# SUP_1V.net
KiCad netlist of a schematic drawn in Altium Designer
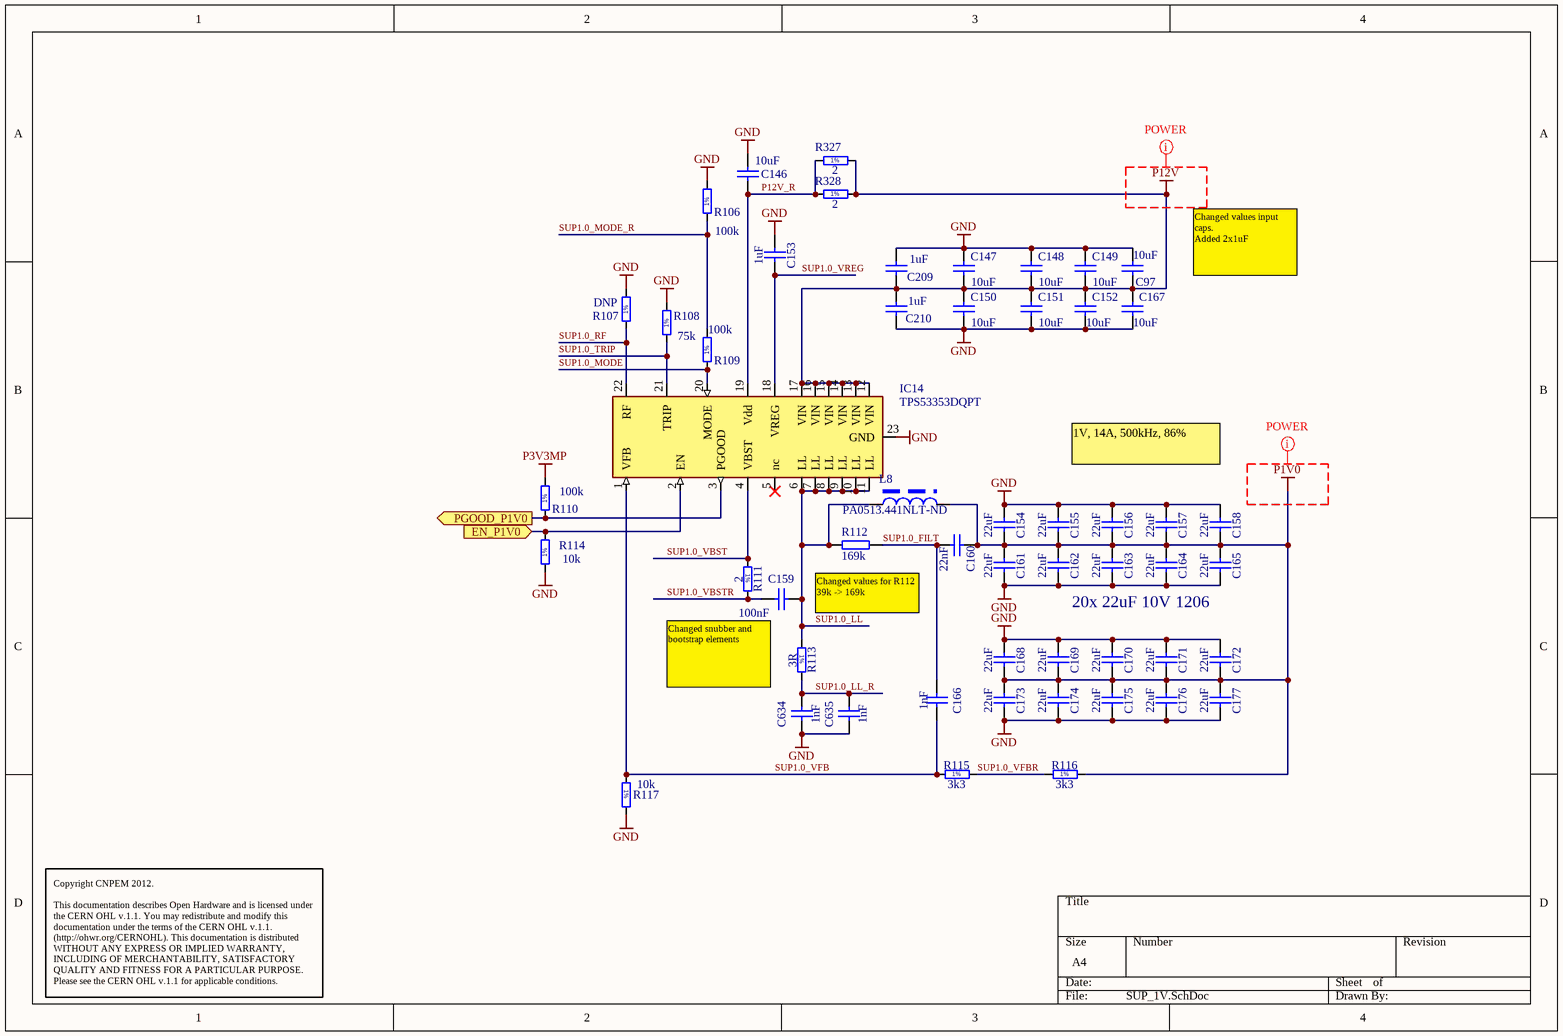
[diagram p0: SUP_1V.SchDoc]

(export (version "E")
  (design (tool "Eeschema 10.0.6"))
  (components
    (comp (ref "C97")
      (value "10uF")
      (footprint "CAPC2012X135N")
      (description "Non-polarised capacitor")
      (fields
        (field (name "PART NUMBER") "CC0805_10UF_16V_10%_X5R")
        (field (name "VOLTAGE") "16V")
        (field (name "AUTHOR") "CERN DEM JLC")
      )
      (libsource (lib "Capacitors") (part "Capacitor - non polarized"))
    )
    (comp (ref "C146")
      (value "10uF")
      (footprint "CAPC2012X135N")
      (description "Non-polarised capacitor")
      (fields
        (field (name "PART NUMBER") "CC0805_10UF_16V_10%_X5R")
        (field (name "VOLTAGE") "16V")
        (field (name "AUTHOR") "CERN DEM JLC")
      )
      (libsource (lib "Capacitors") (part "Capacitor - non polarized"))
    )
    (comp (ref "C147")
      (value "10uF")
      (footprint "CAPC2012X135N")
      (description "Non-polarised capacitor")
      (fields
        (field (name "PART NUMBER") "CC0805_10UF_16V_10%_X5R")
        (field (name "VOLTAGE") "16V")
        (field (name "AUTHOR") "CERN DEM JLC")
      )
      (libsource (lib "Capacitors") (part "Capacitor - non polarized"))
    )
    (comp (ref "C148")
      (value "10uF")
      (footprint "CAPC2012X135N")
      (description "Non-polarised capacitor")
      (fields
        (field (name "PART NUMBER") "CC0805_10UF_16V_10%_X5R")
        (field (name "VOLTAGE") "16V")
        (field (name "AUTHOR") "CERN DEM JLC")
      )
      (libsource (lib "Capacitors") (part "Capacitor - non polarized"))
    )
    (comp (ref "C149")
      (value "10uF")
      (footprint "CAPC2012X135N")
      (description "Non-polarised capacitor")
      (fields
        (field (name "PART NUMBER") "CC0805_10UF_16V_10%_X5R")
        (field (name "VOLTAGE") "16V")
        (field (name "AUTHOR") "CERN DEM JLC")
      )
      (libsource (lib "Capacitors") (part "Capacitor - non polarized"))
    )
    (comp (ref "C150")
      (value "10uF")
      (footprint "CAPC2012X135N")
      (description "Non-polarised capacitor")
      (fields
        (field (name "PART NUMBER") "CC0805_10UF_16V_10%_X5R")
        (field (name "VOLTAGE") "16V")
        (field (name "AUTHOR") "CERN DEM JLC")
      )
      (libsource (lib "Capacitors") (part "Capacitor - non polarized"))
    )
    (comp (ref "C151")
      (value "10uF")
      (footprint "CAPC2012X135N")
      (description "Non-polarised capacitor")
      (fields
        (field (name "PART NUMBER") "CC0805_10UF_16V_10%_X5R")
        (field (name "VOLTAGE") "16V")
        (field (name "AUTHOR") "CERN DEM JLC")
      )
      (libsource (lib "Capacitors") (part "Capacitor - non polarized"))
    )
    (comp (ref "C152")
      (value "10uF")
      (footprint "CAPC2012X135N")
      (description "Non-polarised capacitor")
      (fields
        (field (name "PART NUMBER") "CC0805_10UF_16V_10%_X5R")
        (field (name "VOLTAGE") "16V")
        (field (name "AUTHOR") "CERN DEM JLC")
      )
      (libsource (lib "Capacitors") (part "Capacitor - non polarized"))
    )
    (comp (ref "C153")
      (value "1uF")
      (footprint "CAPC1608X87N")
      (description "Non-polarised capacitor")
      (fields
        (field (name "PART NUMBER") "CC0603_1UF_16V_10%_X7R")
        (field (name "VOLTAGE") "16V")
        (field (name "AUTHOR") "CERN DEM JLC")
      )
      (libsource (lib "Capacitors") (part "Capacitor - non polarized"))
    )
    (comp (ref "C154")
      (value "22uF")
      (footprint "CAPC3216X180N")
      (description "Non-polarised capacitor")
      (fields
        (field (name "PART NUMBER") "CC1206_22UF_10V_10%_X7R")
        (field (name "VOLTAGE") "10V")
        (field (name "AUTHOR") "CERN DEM JLC")
      )
      (libsource (lib "Capacitors") (part "Capacitor - non polarized"))
    )
    (comp (ref "C155")
      (value "22uF")
      (footprint "CAPC3216X180N")
      (description "Non-polarised capacitor")
      (fields
        (field (name "PART NUMBER") "CC1206_22UF_10V_10%_X7R")
        (field (name "VOLTAGE") "10V")
        (field (name "AUTHOR") "CERN DEM JLC")
      )
      (libsource (lib "Capacitors") (part "Capacitor - non polarized"))
    )
    (comp (ref "C156")
      (value "22uF")
      (footprint "CAPC3216X180N")
      (description "Non-polarised capacitor")
      (fields
        (field (name "PART NUMBER") "CC1206_22UF_10V_10%_X7R")
        (field (name "VOLTAGE") "10V")
        (field (name "AUTHOR") "CERN DEM JLC")
      )
      (libsource (lib "Capacitors") (part "Capacitor - non polarized"))
    )
    (comp (ref "C157")
      (value "22uF")
      (footprint "CAPC3216X180N")
      (description "Non-polarised capacitor")
      (fields
        (field (name "PART NUMBER") "CC1206_22UF_10V_10%_X7R")
        (field (name "VOLTAGE") "10V")
        (field (name "AUTHOR") "CERN DEM JLC")
      )
      (libsource (lib "Capacitors") (part "Capacitor - non polarized"))
    )
    (comp (ref "C158")
      (value "22uF")
      (footprint "CAPC3216X180N")
      (description "Non-polarised capacitor")
      (fields
        (field (name "PART NUMBER") "CC1206_22UF_10V_10%_X7R")
        (field (name "VOLTAGE") "10V")
        (field (name "AUTHOR") "CERN DEM JLC")
      )
      (libsource (lib "Capacitors") (part "Capacitor - non polarized"))
    )
    (comp (ref "C159")
      (value "100nF")
      (footprint "CAPC1005X55N")
      (description "Non-polarised capacitor")
      (fields
        (field (name "PART NUMBER") "CC0402_100NF_16V_10%_X7R")
        (field (name "VOLTAGE") "16V")
        (field (name "AUTHOR") "CERN DEM JLC")
      )
      (libsource (lib "Capacitors") (part "Capacitor - non polarized"))
    )
    (comp (ref "C160")
      (value "22nF")
      (footprint "CAPC1608X87N")
      (description "Non-polarised capacitor")
      (fields
        (field (name "PART NUMBER") "CC0603_22NF_50V_10%_X7R")
        (field (name "VOLTAGE") "50V")
        (field (name "AUTHOR") "CERN DEM JLC")
      )
      (libsource (lib "Capacitors") (part "Capacitor - non polarized"))
    )
    (comp (ref "C161")
      (value "22uF")
      (footprint "CAPC3216X180N")
      (description "Non-polarised capacitor")
      (fields
        (field (name "PART NUMBER") "CC1206_22UF_10V_10%_X7R")
        (field (name "VOLTAGE") "10V")
        (field (name "AUTHOR") "CERN DEM JLC")
      )
      (libsource (lib "Capacitors") (part "Capacitor - non polarized"))
    )
    (comp (ref "C162")
      (value "22uF")
      (footprint "CAPC3216X180N")
      (description "Non-polarised capacitor")
      (fields
        (field (name "PART NUMBER") "CC1206_22UF_10V_10%_X7R")
        (field (name "VOLTAGE") "10V")
        (field (name "AUTHOR") "CERN DEM JLC")
      )
      (libsource (lib "Capacitors") (part "Capacitor - non polarized"))
    )
    (comp (ref "C163")
      (value "22uF")
      (footprint "CAPC3216X180N")
      (description "Non-polarised capacitor")
      (fields
        (field (name "PART NUMBER") "CC1206_22UF_10V_10%_X7R")
        (field (name "VOLTAGE") "10V")
        (field (name "AUTHOR") "CERN DEM JLC")
      )
      (libsource (lib "Capacitors") (part "Capacitor - non polarized"))
    )
    (comp (ref "C164")
      (value "22uF")
      (footprint "CAPC3216X180N")
      (description "Non-polarised capacitor")
      (fields
        (field (name "PART NUMBER") "CC1206_22UF_10V_10%_X7R")
        (field (name "VOLTAGE") "10V")
        (field (name "AUTHOR") "CERN DEM JLC")
      )
      (libsource (lib "Capacitors") (part "Capacitor - non polarized"))
    )
    (comp (ref "C165")
      (value "22uF")
      (footprint "CAPC3216X180N")
      (description "Non-polarised capacitor")
      (fields
        (field (name "PART NUMBER") "CC1206_22UF_10V_10%_X7R")
        (field (name "VOLTAGE") "10V")
        (field (name "AUTHOR") "CERN DEM JLC")
      )
      (libsource (lib "Capacitors") (part "Capacitor - non polarized"))
    )
    (comp (ref "C166")
      (value "1nF")
      (footprint "CAPC1005X55N")
      (description "Non-polarised capacitor")
      (fields
        (field (name "PART NUMBER") "CC0402_1NF_50V_10%_X7R")
        (field (name "VOLTAGE") "50V")
        (field (name "AUTHOR") "CERN DEM JLC")
      )
      (libsource (lib "Capacitors") (part "Capacitor - non polarized"))
    )
    (comp (ref "C167")
      (value "10uF")
      (footprint "CAPC2012X135N")
      (description "Non-polarised capacitor")
      (fields
        (field (name "PART NUMBER") "CC0805_10UF_16V_10%_X5R")
        (field (name "VOLTAGE") "16V")
        (field (name "AUTHOR") "CERN DEM JLC")
      )
      (libsource (lib "Capacitors") (part "Capacitor - non polarized"))
    )
    (comp (ref "C168")
      (value "22uF")
      (footprint "CAPC3216X180N")
      (description "Non-polarised capacitor")
      (fields
        (field (name "PART NUMBER") "CC1206_22UF_10V_10%_X7R")
        (field (name "VOLTAGE") "10V")
        (field (name "AUTHOR") "CERN DEM JLC")
      )
      (libsource (lib "Capacitors") (part "Capacitor - non polarized"))
    )
    (comp (ref "C169")
      (value "22uF")
      (footprint "CAPC3216X180N")
      (description "Non-polarised capacitor")
      (fields
        (field (name "PART NUMBER") "CC1206_22UF_10V_10%_X7R")
        (field (name "VOLTAGE") "10V")
        (field (name "AUTHOR") "CERN DEM JLC")
      )
      (libsource (lib "Capacitors") (part "Capacitor - non polarized"))
    )
    (comp (ref "C170")
      (value "22uF")
      (footprint "CAPC3216X180N")
      (description "Non-polarised capacitor")
      (fields
        (field (name "PART NUMBER") "CC1206_22UF_10V_10%_X7R")
        (field (name "VOLTAGE") "10V")
        (field (name "AUTHOR") "CERN DEM JLC")
      )
      (libsource (lib "Capacitors") (part "Capacitor - non polarized"))
    )
    (comp (ref "C171")
      (value "22uF")
      (footprint "CAPC3216X180N")
      (description "Non-polarised capacitor")
      (fields
        (field (name "PART NUMBER") "CC1206_22UF_10V_10%_X7R")
        (field (name "VOLTAGE") "10V")
        (field (name "AUTHOR") "CERN DEM JLC")
      )
      (libsource (lib "Capacitors") (part "Capacitor - non polarized"))
    )
    (comp (ref "C172")
      (value "22uF")
      (footprint "CAPC3216X180N")
      (description "Non-polarised capacitor")
      (fields
        (field (name "PART NUMBER") "CC1206_22UF_10V_10%_X7R")
        (field (name "VOLTAGE") "10V")
        (field (name "AUTHOR") "CERN DEM JLC")
      )
      (libsource (lib "Capacitors") (part "Capacitor - non polarized"))
    )
    (comp (ref "C173")
      (value "22uF")
      (footprint "CAPC3216X180N")
      (description "Non-polarised capacitor")
      (fields
        (field (name "PART NUMBER") "CC1206_22UF_10V_10%_X7R")
        (field (name "VOLTAGE") "10V")
        (field (name "AUTHOR") "CERN DEM JLC")
      )
      (libsource (lib "Capacitors") (part "Capacitor - non polarized"))
    )
    (comp (ref "C174")
      (value "22uF")
      (footprint "CAPC3216X180N")
      (description "Non-polarised capacitor")
      (fields
        (field (name "PART NUMBER") "CC1206_22UF_10V_10%_X7R")
        (field (name "VOLTAGE") "10V")
        (field (name "AUTHOR") "CERN DEM JLC")
      )
      (libsource (lib "Capacitors") (part "Capacitor - non polarized"))
    )
    (comp (ref "C175")
      (value "22uF")
      (footprint "CAPC3216X180N")
      (description "Non-polarised capacitor")
      (fields
        (field (name "PART NUMBER") "CC1206_22UF_10V_10%_X7R")
        (field (name "VOLTAGE") "10V")
        (field (name "AUTHOR") "CERN DEM JLC")
      )
      (libsource (lib "Capacitors") (part "Capacitor - non polarized"))
    )
    (comp (ref "C176")
      (value "22uF")
      (footprint "CAPC3216X180N")
      (description "Non-polarised capacitor")
      (fields
        (field (name "PART NUMBER") "CC1206_22UF_10V_10%_X7R")
        (field (name "VOLTAGE") "10V")
        (field (name "AUTHOR") "CERN DEM JLC")
      )
      (libsource (lib "Capacitors") (part "Capacitor - non polarized"))
    )
    (comp (ref "C177")
      (value "22uF")
      (footprint "CAPC3216X180N")
      (description "Non-polarised capacitor")
      (fields
        (field (name "PART NUMBER") "CC1206_22UF_10V_10%_X7R")
        (field (name "VOLTAGE") "10V")
        (field (name "AUTHOR") "CERN DEM JLC")
      )
      (libsource (lib "Capacitors") (part "Capacitor - non polarized"))
    )
    (comp (ref "C209")
      (value "1uF")
      (footprint "CAPC1608X87N")
      (description "Non-polarised capacitor")
      (fields
        (field (name "PART NUMBER") "CC0603_1UF_16V_10%_X7R")
        (field (name "VOLTAGE") "16V")
        (field (name "AUTHOR") "CERN DEM JLC")
      )
      (libsource (lib "Capacitors") (part "Capacitor - non polarized"))
    )
    (comp (ref "C210")
      (value "1uF")
      (footprint "CAPC1608X87N")
      (description "Non-polarised capacitor")
      (fields
        (field (name "PART NUMBER") "CC0603_1UF_16V_10%_X7R")
        (field (name "VOLTAGE") "16V")
        (field (name "AUTHOR") "CERN DEM JLC")
      )
      (libsource (lib "Capacitors") (part "Capacitor - non polarized"))
    )
    (comp (ref "C634")
      (value "1nF")
      (footprint "CAPC1005X55N")
      (description "Non-polarised capacitor")
      (fields
        (field (name "PART NUMBER") "CC0402_1NF_50V_10%_X7R")
        (field (name "VOLTAGE") "50V")
        (field (name "AUTHOR") "CERN DEM JLC")
      )
      (libsource (lib "Capacitors") (part "Capacitor - non polarized"))
    )
    (comp (ref "C635")
      (value "1nF")
      (footprint "CAPC1005X55N")
      (description "Non-polarised capacitor")
      (fields
        (field (name "PART NUMBER") "CC0402_1NF_50V_10%_X7R")
        (field (name "VOLTAGE") "50V")
        (field (name "AUTHOR") "CERN DEM JLC")
      )
      (libsource (lib "Capacitors") (part "Capacitor - non polarized"))
    )
    (comp (ref "IC14")
      (value "TPS53353DQPT")
      (footprint "LCCS50P600X500X150-22N")
      (description "High-Efficiency 20-A Synchronous Buck Converter with Eco-mode™")
      (libsource (lib "LIBRARY_SCH") (part "PM_TPS53353"))
    )
    (comp (ref "L8")
      (value "PA0513.441NLT-ND")
      (footprint "IND_PA0513")
      (description "440nH, 30A, 0.32mOhm")
      (libsource (lib "LIBRARY_SCH") (part "L_POWER_PA1513_440nH"))
    )
    (comp (ref "R106")
      (value "100k")
      (footprint "RESC1005X40N")
      (description "Resistor - 1%")
      (fields
        (field (name "PART NUMBER") "R0402_100K_1%_0.0625W_100PPM")
        (field (name "POWER") "0.0625W")
        (field (name "AUTHOR") "CERN DEM JLC")
      )
      (libsource (lib "Resistors") (part "Resistor - 1%"))
    )
    (comp (ref "R107")
      (value "DNP")
      (footprint "RESC1608X55N")
      (description "Resistor - 1%")
      (fields
        (field (name "PART NUMBER") "R0603_75K_1%_0.1W_100PPM")
        (field (name "POWER") "0.1W")
        (field (name "AUTHOR") "CERN DEM JLC")
      )
      (libsource (lib "Resistors") (part "Resistor - 1%"))
    )
    (comp (ref "R108")
      (value "75k")
      (footprint "RESC1608X55N")
      (description "Resistor - 1%")
      (fields
        (field (name "PART NUMBER") "R0603_75K_1%_0.1W_100PPM")
        (field (name "POWER") "0.1W")
        (field (name "AUTHOR") "CERN DEM JLC")
      )
      (libsource (lib "Resistors") (part "Resistor - 1%"))
    )
    (comp (ref "R109")
      (value "100k")
      (footprint "RESC1005X40N")
      (description "Resistor - 1%")
      (fields
        (field (name "PART NUMBER") "R0402_100K_1%_0.0625W_100PPM")
        (field (name "POWER") "0.0625W")
        (field (name "AUTHOR") "CERN DEM JLC")
      )
      (libsource (lib "Resistors") (part "Resistor - 1%"))
    )
    (comp (ref "R110")
      (value "100k")
      (footprint "RESC1005X40N")
      (description "Resistor - 1%")
      (fields
        (field (name "PART NUMBER") "R0402_100K_1%_0.0625W_100PPM")
        (field (name "POWER") "0.0625W")
        (field (name "AUTHOR") "CERN DEM JLC")
      )
      (libsource (lib "Resistors") (part "Resistor - 1%"))
    )
    (comp (ref "R111")
      (value "2")
      (footprint "RESC1608X55N")
      (description "Resistor - 1%")
      (fields
        (field (name "PART NUMBER") "R0603_2R_1%_0.1W_200PPM")
        (field (name "POWER") "0.1W")
        (field (name "AUTHOR") "CERN DEM JLC")
      )
      (libsource (lib "Resistors") (part "Resistor - 1%"))
    )
    (comp (ref "R112")
      (value "169k")
      (footprint "0603R")
      (description "SMD Resistor")
      (libsource (lib "LIBRARY_SCH") (part "RES_0603"))
    )
    (comp (ref "R113")
      (value "3R")
      (footprint "RESC3216X65N")
      (description "Resistor - 1%")
      (fields
        (field (name "PART NUMBER") "R1206_3R_1%_0.25W_200PPM")
        (field (name "POWER") "0.25W")
        (field (name "AUTHOR") "CERN DEM JLC")
      )
      (libsource (lib "Resistors") (part "Resistor - 1%"))
    )
    (comp (ref "R114")
      (value "10k")
      (footprint "RESC1005X40N")
      (description "Resistor - 1%")
      (fields
        (field (name "PART NUMBER") "R0402_10K_1%_0.0625W_100PPM")
        (field (name "POWER") "0.0625W")
        (field (name "AUTHOR") "CERN DEM JLC")
      )
      (libsource (lib "Resistors") (part "Resistor - 1%"))
    )
    (comp (ref "R115")
      (value "3k3")
      (footprint "RESC1608X55N")
      (description "Resistor - 1%")
      (fields
        (field (name "PART NUMBER") "R0603_3K3_1%_0.1W_100PPM")
        (field (name "POWER") "0.1W")
        (field (name "AUTHOR") "CERN DEM JLC")
      )
      (libsource (lib "Resistors") (part "Resistor - 1%"))
    )
    (comp (ref "R116")
      (value "3k3")
      (footprint "RESC1608X55N")
      (description "Resistor - 1%")
      (fields
        (field (name "PART NUMBER") "R0603_3K3_1%_0.1W_100PPM")
        (field (name "POWER") "0.1W")
        (field (name "AUTHOR") "CERN DEM JLC")
      )
      (libsource (lib "Resistors") (part "Resistor - 1%"))
    )
    (comp (ref "R117")
      (value "10k")
      (footprint "RESC1005X40N")
      (description "Resistor - 1%")
      (fields
        (field (name "PART NUMBER") "R0402_10K_1%_0.0625W_100PPM")
        (field (name "POWER") "0.0625W")
        (field (name "AUTHOR") "CERN DEM JLC")
      )
      (libsource (lib "Resistors") (part "Resistor - 1%"))
    )
    (comp (ref "R327")
      (value "2")
      (footprint "RESC1608X55N")
      (description "Resistor - 1%")
      (fields
        (field (name "PART NUMBER") "R0603_2R_1%_0.1W_200PPM")
        (field (name "POWER") "0.1W")
        (field (name "AUTHOR") "CERN DEM JLC")
      )
      (libsource (lib "Resistors") (part "Resistor - 1%"))
    )
    (comp (ref "R328")
      (value "2")
      (footprint "RESC1608X55N")
      (description "Resistor - 1%")
      (fields
        (field (name "PART NUMBER") "R0603_2R_1%_0.1W_200PPM")
        (field (name "POWER") "0.1W")
        (field (name "AUTHOR") "CERN DEM JLC")
      )
      (libsource (lib "Resistors") (part "Resistor - 1%"))
    )
  )
  (nets
    (net (code "1") (name "/EN_P1V0") (class "Default")
      (node (ref "IC14") (pin "2") (pinfunction "EN_2") (pintype "input"))
      (node (ref "R114") (pin "2") (pinfunction "2_2") (pintype "passive"))
    )
    (net (code "2") (name "/P12V_R") (class "Default")
      (node (ref "C146") (pin "1") (pinfunction "1_1") (pintype "passive"))
      (node (ref "IC14") (pin "19") (pinfunction "Vdd_19") (pintype "power_in"))
      (node (ref "R327") (pin "1") (pinfunction "1_1") (pintype "passive"))
      (node (ref "R328") (pin "1") (pinfunction "1_1") (pintype "passive"))
    )
    (net (code "3") (name "/PGOOD_P1V0") (class "Default")
      (node (ref "IC14") (pin "3") (pinfunction "PGOOD_3") (pintype "output"))
      (node (ref "R110") (pin "1") (pinfunction "1_1") (pintype "passive"))
    )
    (net (code "4") (name "/SUP1.0_FILT") (class "Default")
      (node (ref "C160") (pin "1") (pinfunction "1_1") (pintype "passive"))
      (node (ref "C166") (pin "2") (pinfunction "2_2") (pintype "passive"))
      (node (ref "R112") (pin "1") (pinfunction "1_1") (pintype "passive"))
    )
    (net (code "5") (name "/SUP1.0_LL") (class "Default")
      (node (ref "C159") (pin "1") (pinfunction "1_1") (pintype "passive"))
      (node (ref "IC14") (pin "10") (pinfunction "LL_10") (pintype "passive"))
      (node (ref "IC14") (pin "11") (pinfunction "LL_11") (pintype "passive"))
      (node (ref "IC14") (pin "6") (pinfunction "LL_6") (pintype "passive"))
      (node (ref "IC14") (pin "7") (pinfunction "LL_7") (pintype "passive"))
      (node (ref "IC14") (pin "8") (pinfunction "LL_8") (pintype "passive"))
      (node (ref "IC14") (pin "9") (pinfunction "LL_9") (pintype "passive"))
      (node (ref "L8") (pin "1") (pintype "passive"))
      (node (ref "R112") (pin "2") (pinfunction "2_2") (pintype "passive"))
      (node (ref "R113") (pin "1") (pinfunction "1_1") (pintype "passive"))
    )
    (net (code "6") (name "/SUP1.0_LL_R") (class "Default")
      (node (ref "C634") (pin "1") (pinfunction "1_1") (pintype "passive"))
      (node (ref "C635") (pin "1") (pinfunction "1_1") (pintype "passive"))
      (node (ref "R113") (pin "2") (pinfunction "2_2") (pintype "passive"))
    )
    (net (code "7") (name "/SUP1.0_MODE") (class "Default")
      (node (ref "IC14") (pin "20") (pinfunction "MODE_20") (pintype "input"))
      (node (ref "R109") (pin "1") (pinfunction "1_1") (pintype "passive"))
    )
    (net (code "8") (name "/SUP1.0_MODE_R") (class "Default")
      (node (ref "R106") (pin "1") (pinfunction "1_1") (pintype "passive"))
      (node (ref "R109") (pin "2") (pinfunction "2_2") (pintype "passive"))
    )
    (net (code "9") (name "/SUP1.0_RF") (class "Default")
      (node (ref "IC14") (pin "22") (pinfunction "RF_22") (pintype "passive"))
      (node (ref "R107") (pin "1") (pinfunction "1_1") (pintype "passive"))
    )
    (net (code "10") (name "/SUP1.0_TRIP") (class "Default")
      (node (ref "IC14") (pin "21") (pinfunction "TRIP_21") (pintype "passive"))
      (node (ref "R108") (pin "1") (pinfunction "1_1") (pintype "passive"))
    )
    (net (code "11") (name "/SUP1.0_VBST") (class "Default")
      (node (ref "IC14") (pin "4") (pinfunction "VBST_4") (pintype "passive"))
      (node (ref "R111") (pin "1") (pinfunction "1_1") (pintype "passive"))
    )
    (net (code "12") (name "/SUP1.0_VBSTR") (class "Default")
      (node (ref "C159") (pin "2") (pinfunction "2_2") (pintype "passive"))
      (node (ref "R111") (pin "2") (pinfunction "2_2") (pintype "passive"))
    )
    (net (code "13") (name "/SUP1.0_VFB") (class "Default")
      (node (ref "C166") (pin "1") (pinfunction "1_1") (pintype "passive"))
      (node (ref "IC14") (pin "1") (pinfunction "VFB_1") (pintype "input"))
      (node (ref "R115") (pin "1") (pinfunction "1_1") (pintype "passive"))
      (node (ref "R117") (pin "1") (pinfunction "1_1") (pintype "passive"))
    )
    (net (code "14") (name "/SUP1.0_VFBR") (class "Default")
      (node (ref "R115") (pin "2") (pinfunction "2_2") (pintype "passive"))
      (node (ref "R116") (pin "1") (pinfunction "1_1") (pintype "passive"))
    )
    (net (code "15") (name "/SUP1.0_VREG") (class "Default")
      (node (ref "C153") (pin "2") (pinfunction "2_2") (pintype "passive"))
      (node (ref "IC14") (pin "18") (pinfunction "VREG_18") (pintype "power_in"))
    )
    (net (code "16") (name "GND") (class "Default")
      (node (ref "C146") (pin "2") (pinfunction "2_2") (pintype "passive"))
      (node (ref "C147") (pin "2") (pinfunction "2_2") (pintype "passive"))
      (node (ref "C148") (pin "2") (pinfunction "2_2") (pintype "passive"))
      (node (ref "C149") (pin "2") (pinfunction "2_2") (pintype "passive"))
      (node (ref "C150") (pin "1") (pinfunction "1_1") (pintype "passive"))
      (node (ref "C151") (pin "1") (pinfunction "1_1") (pintype "passive"))
      (node (ref "C152") (pin "1") (pinfunction "1_1") (pintype "passive"))
      (node (ref "C153") (pin "1") (pinfunction "1_1") (pintype "passive"))
      (node (ref "C154") (pin "1") (pinfunction "1_1") (pintype "passive"))
      (node (ref "C155") (pin "1") (pinfunction "1_1") (pintype "passive"))
      (node (ref "C156") (pin "1") (pinfunction "1_1") (pintype "passive"))
      (node (ref "C157") (pin "1") (pinfunction "1_1") (pintype "passive"))
      (node (ref "C158") (pin "1") (pinfunction "1_1") (pintype "passive"))
      (node (ref "C161") (pin "2") (pinfunction "2_2") (pintype "passive"))
      (node (ref "C162") (pin "2") (pinfunction "2_2") (pintype "passive"))
      (node (ref "C163") (pin "2") (pinfunction "2_2") (pintype "passive"))
      (node (ref "C164") (pin "2") (pinfunction "2_2") (pintype "passive"))
      (node (ref "C165") (pin "2") (pinfunction "2_2") (pintype "passive"))
      (node (ref "C167") (pin "1") (pinfunction "1_1") (pintype "passive"))
      (node (ref "C168") (pin "1") (pinfunction "1_1") (pintype "passive"))
      (node (ref "C169") (pin "1") (pinfunction "1_1") (pintype "passive"))
      (node (ref "C170") (pin "1") (pinfunction "1_1") (pintype "passive"))
      (node (ref "C171") (pin "1") (pinfunction "1_1") (pintype "passive"))
      (node (ref "C172") (pin "1") (pinfunction "1_1") (pintype "passive"))
      (node (ref "C173") (pin "2") (pinfunction "2_2") (pintype "passive"))
      (node (ref "C174") (pin "2") (pinfunction "2_2") (pintype "passive"))
      (node (ref "C175") (pin "2") (pinfunction "2_2") (pintype "passive"))
      (node (ref "C176") (pin "2") (pinfunction "2_2") (pintype "passive"))
      (node (ref "C177") (pin "2") (pinfunction "2_2") (pintype "passive"))
      (node (ref "C209") (pin "2") (pinfunction "2_2") (pintype "passive"))
      (node (ref "C210") (pin "1") (pinfunction "1_1") (pintype "passive"))
      (node (ref "C634") (pin "2") (pinfunction "2_2") (pintype "passive"))
      (node (ref "C635") (pin "2") (pinfunction "2_2") (pintype "passive"))
      (node (ref "C97") (pin "1") (pinfunction "1_1") (pintype "passive"))
      (node (ref "IC14") (pin "23") (pinfunction "GND_23") (pintype "power_in"))
      (node (ref "R106") (pin "2") (pinfunction "2_2") (pintype "passive"))
      (node (ref "R107") (pin "2") (pinfunction "2_2") (pintype "passive"))
      (node (ref "R108") (pin "2") (pinfunction "2_2") (pintype "passive"))
      (node (ref "R114") (pin "1") (pinfunction "1_1") (pintype "passive"))
      (node (ref "R117") (pin "2") (pinfunction "2_2") (pintype "passive"))
    )
    (net (code "17") (name "P1V0") (class "Default")
      (node (ref "C154") (pin "2") (pinfunction "2_2") (pintype "passive"))
      (node (ref "C155") (pin "2") (pinfunction "2_2") (pintype "passive"))
      (node (ref "C156") (pin "2") (pinfunction "2_2") (pintype "passive"))
      (node (ref "C157") (pin "2") (pinfunction "2_2") (pintype "passive"))
      (node (ref "C158") (pin "2") (pinfunction "2_2") (pintype "passive"))
      (node (ref "C160") (pin "2") (pinfunction "2_2") (pintype "passive"))
      (node (ref "C161") (pin "1") (pinfunction "1_1") (pintype "passive"))
      (node (ref "C162") (pin "1") (pinfunction "1_1") (pintype "passive"))
      (node (ref "C163") (pin "1") (pinfunction "1_1") (pintype "passive"))
      (node (ref "C164") (pin "1") (pinfunction "1_1") (pintype "passive"))
      (node (ref "C165") (pin "1") (pinfunction "1_1") (pintype "passive"))
      (node (ref "C168") (pin "2") (pinfunction "2_2") (pintype "passive"))
      (node (ref "C169") (pin "2") (pinfunction "2_2") (pintype "passive"))
      (node (ref "C170") (pin "2") (pinfunction "2_2") (pintype "passive"))
      (node (ref "C171") (pin "2") (pinfunction "2_2") (pintype "passive"))
      (node (ref "C172") (pin "2") (pinfunction "2_2") (pintype "passive"))
      (node (ref "C173") (pin "1") (pinfunction "1_1") (pintype "passive"))
      (node (ref "C174") (pin "1") (pinfunction "1_1") (pintype "passive"))
      (node (ref "C175") (pin "1") (pinfunction "1_1") (pintype "passive"))
      (node (ref "C176") (pin "1") (pinfunction "1_1") (pintype "passive"))
      (node (ref "C177") (pin "1") (pinfunction "1_1") (pintype "passive"))
      (node (ref "L8") (pin "2") (pintype "passive"))
      (node (ref "R116") (pin "2") (pinfunction "2_2") (pintype "passive"))
    )
    (net (code "18") (name "P3V3MP") (class "Default")
      (node (ref "R110") (pin "2") (pinfunction "2_2") (pintype "passive"))
    )
    (net (code "19") (name "P12V") (class "Default")
      (node (ref "C147") (pin "1") (pinfunction "1_1") (pintype "passive"))
      (node (ref "C148") (pin "1") (pinfunction "1_1") (pintype "passive"))
      (node (ref "C149") (pin "1") (pinfunction "1_1") (pintype "passive"))
      (node (ref "C150") (pin "2") (pinfunction "2_2") (pintype "passive"))
      (node (ref "C151") (pin "2") (pinfunction "2_2") (pintype "passive"))
      (node (ref "C152") (pin "2") (pinfunction "2_2") (pintype "passive"))
      (node (ref "C167") (pin "2") (pinfunction "2_2") (pintype "passive"))
      (node (ref "C209") (pin "1") (pinfunction "1_1") (pintype "passive"))
      (node (ref "C210") (pin "2") (pinfunction "2_2") (pintype "passive"))
      (node (ref "C97") (pin "2") (pinfunction "2_2") (pintype "passive"))
      (node (ref "IC14") (pin "12") (pinfunction "VIN_12") (pintype "power_in"))
      (node (ref "IC14") (pin "13") (pinfunction "VIN_13") (pintype "power_in"))
      (node (ref "IC14") (pin "14") (pinfunction "VIN_14") (pintype "power_in"))
      (node (ref "IC14") (pin "15") (pinfunction "VIN_15") (pintype "power_in"))
      (node (ref "IC14") (pin "16") (pinfunction "VIN_16") (pintype "power_in"))
      (node (ref "IC14") (pin "17") (pinfunction "VIN_17") (pintype "power_in"))
      (node (ref "R327") (pin "2") (pinfunction "2_2") (pintype "passive"))
      (node (ref "R328") (pin "2") (pinfunction "2_2") (pintype "passive"))
    )
    (net (code "20") (name "unconnected-(IC14-nc-Pad5)") (class "Default")
      (node (ref "IC14") (pin "5") (pinfunction "nc_5") (pintype "passive+no_connect"))
    )
  )
)
